# Audio-Out.net
KiCad netlist of a schematic drawn in Altium Designer
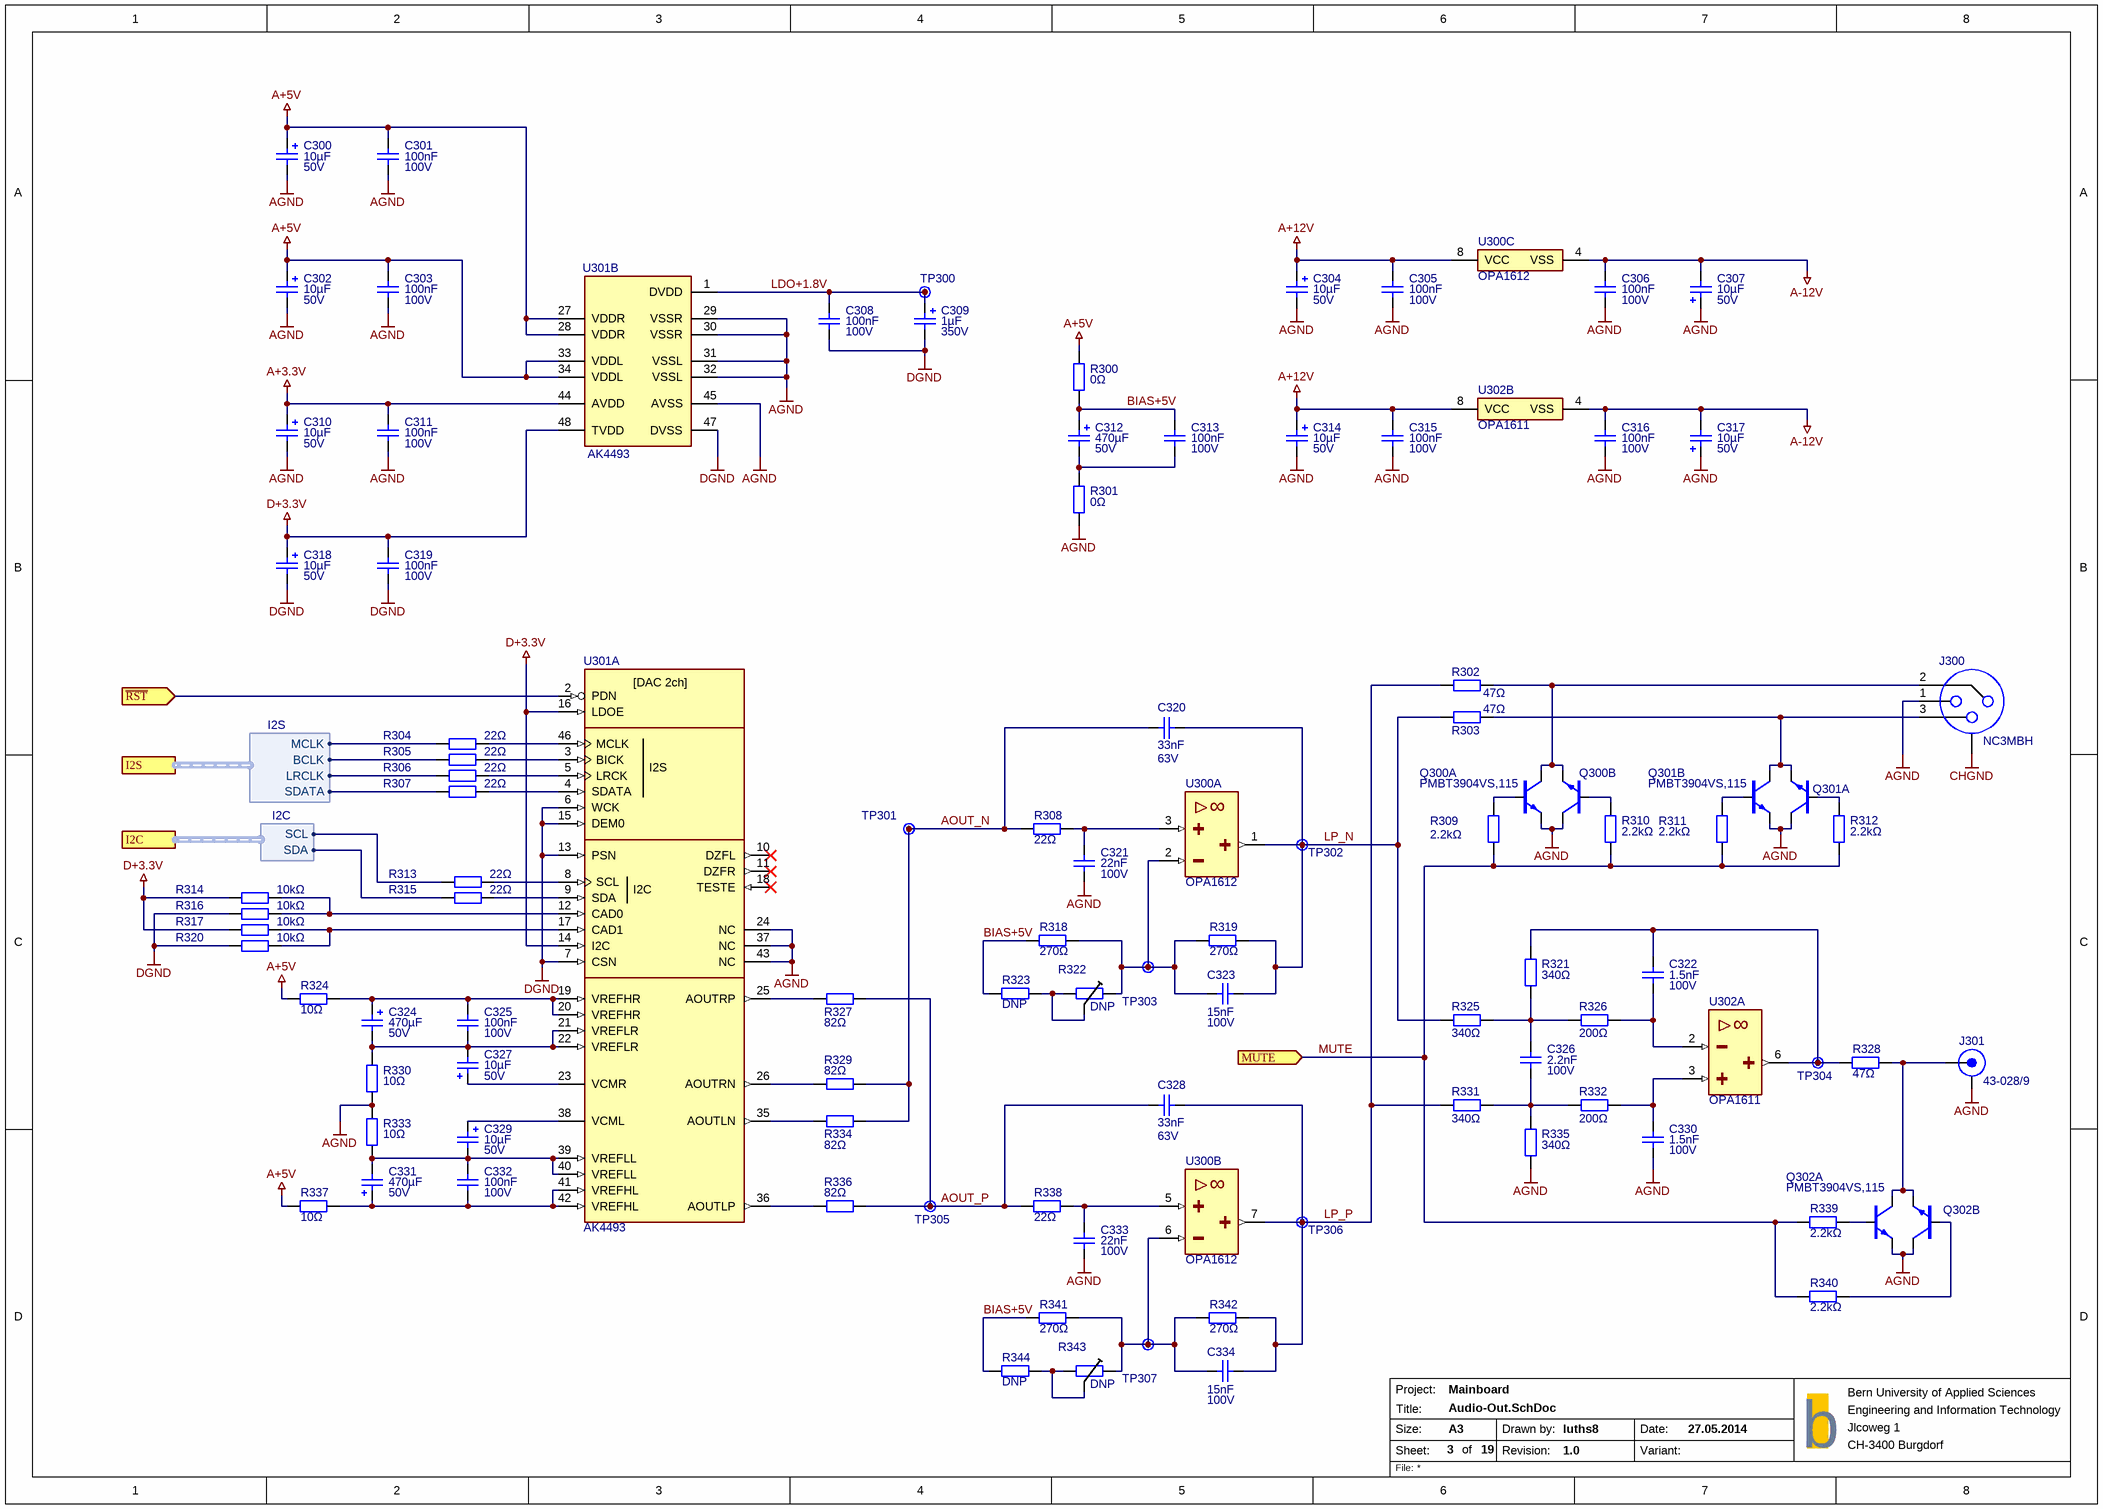
[diagram p0: Audio-Out.SchDoc]

(export (version "E")
  (design (tool "Eeschema 10.0.6"))
  (components
    (comp (ref "C300")
      (value "10µF")
      (footprint "CAP-5-11.5-2")
      (description "Elektrolytic Capacitor")
      (fields (field (name "VOLTAGE") "50V") (field (name "MANUFACTURER PART NO.") "EEU-FR1H100"))
      (libsource (lib "Audio-Streamer") (part "Capacitor Electrolytic"))
    )
    (comp (ref "C301")
      (value "100nF")
      (footprint "CAP_WIMA_MKP4F")
      (description "Ceramic Capacitor")
      (fields (field (name "VOLTAGE") "100V") (field (name "MANUFACTURER PART NO.") "MKP2D031001F00KF00"))
      (libsource (lib "Audio-Streamer") (part "Capacitor Ceramic"))
    )
    (comp (ref "C302")
      (value "10µF")
      (footprint "CAP-5-11.5-2")
      (description "Elektrolytic Capacitor")
      (fields (field (name "VOLTAGE") "50V") (field (name "MANUFACTURER PART NO.") "EEU-FR1H100"))
      (libsource (lib "Audio-Streamer") (part "Capacitor Electrolytic"))
    )
    (comp (ref "C303")
      (value "100nF")
      (footprint "CAP_WIMA_MKP4F")
      (description "Ceramic Capacitor")
      (fields (field (name "VOLTAGE") "100V") (field (name "MANUFACTURER PART NO.") "MKP2D031001F00KF00"))
      (libsource (lib "Audio-Streamer") (part "Capacitor Ceramic"))
    )
    (comp (ref "C304")
      (value "10µF")
      (footprint "CAP-5-11.5-2")
      (description "Elektrolytic Capacitor")
      (fields (field (name "VOLTAGE") "50V") (field (name "MANUFACTURER PART NO.") "EEU-FR1H100"))
      (libsource (lib "Audio-Streamer") (part "Capacitor Electrolytic"))
    )
    (comp (ref "C305")
      (value "100nF")
      (footprint "CAP_WIMA_MKP4F")
      (description "Ceramic Capacitor")
      (fields (field (name "VOLTAGE") "100V") (field (name "MANUFACTURER PART NO.") "MKP2D031001F00KF00"))
      (libsource (lib "Audio-Streamer") (part "Capacitor Ceramic"))
    )
    (comp (ref "C306")
      (value "100nF")
      (footprint "CAP_WIMA_MKP4F")
      (description "Ceramic Capacitor")
      (fields (field (name "VOLTAGE") "100V") (field (name "MANUFACTURER PART NO.") "MKP2D031001F00KF00"))
      (libsource (lib "Audio-Streamer") (part "Capacitor Ceramic"))
    )
    (comp (ref "C307")
      (value "10µF")
      (footprint "CAP-5-11.5-2")
      (description "Elektrolytic Capacitor")
      (fields (field (name "VOLTAGE") "50V") (field (name "MANUFACTURER PART NO.") "EEU-FR1H100"))
      (libsource (lib "Audio-Streamer") (part "Capacitor Electrolytic"))
    )
    (comp (ref "C308")
      (value "100nF")
      (footprint "CAP_WIMA_MKP4F")
      (description "Ceramic Capacitor")
      (fields (field (name "VOLTAGE") "100V") (field (name "MANUFACTURER PART NO.") "MKP2D031001F00KF00"))
      (libsource (lib "Audio-Streamer") (part "Capacitor Ceramic"))
    )
    (comp (ref "C309")
      (value "1µF")
      (footprint "CAP-6.3-11.2-2.5")
      (description "Elektrolytic Capacitor")
      (fields (field (name "VOLTAGE") "350V"))
      (libsource (lib "Audio-Streamer") (part "Capacitor Electrolytic"))
    )
    (comp (ref "C310")
      (value "10µF")
      (footprint "CAP-5-11.5-2")
      (description "Elektrolytic Capacitor")
      (fields (field (name "VOLTAGE") "50V") (field (name "MANUFACTURER PART NO.") "EEU-FR1H100"))
      (libsource (lib "Audio-Streamer") (part "Capacitor Electrolytic"))
    )
    (comp (ref "C311")
      (value "100nF")
      (footprint "CAP_WIMA_MKP4F")
      (description "Ceramic Capacitor")
      (fields (field (name "VOLTAGE") "100V") (field (name "MANUFACTURER PART NO.") "MKP2D031001F00KF00"))
      (libsource (lib "Audio-Streamer") (part "Capacitor Ceramic"))
    )
    (comp (ref "C312")
      (value "470µF")
      (footprint "CAP-12.5-20-5")
      (description "Elektrolytic Capacitor")
      (fields (field (name "VOLTAGE") "50V") (field (name "MANUFACTURER PART NO.") "EEU-FR1H471"))
      (libsource (lib "Audio-Streamer") (part "Capacitor Electrolytic"))
    )
    (comp (ref "C313")
      (value "100nF")
      (footprint "CAP_WIMA_MKP4F")
      (description "Ceramic Capacitor")
      (fields (field (name "VOLTAGE") "100V") (field (name "MANUFACTURER PART NO.") "MKP2D031001F00KF00"))
      (libsource (lib "Audio-Streamer") (part "Capacitor Ceramic"))
    )
    (comp (ref "C314")
      (value "10µF")
      (footprint "CAP-5-11.5-2")
      (description "Elektrolytic Capacitor")
      (fields (field (name "VOLTAGE") "50V") (field (name "MANUFACTURER PART NO.") "EEU-FR1H100"))
      (libsource (lib "Audio-Streamer") (part "Capacitor Electrolytic"))
    )
    (comp (ref "C315")
      (value "100nF")
      (footprint "CAP_WIMA_MKP4F")
      (description "Ceramic Capacitor")
      (fields (field (name "VOLTAGE") "100V") (field (name "MANUFACTURER PART NO.") "MKP2D031001F00KF00"))
      (libsource (lib "Audio-Streamer") (part "Capacitor Ceramic"))
    )
    (comp (ref "C316")
      (value "100nF")
      (footprint "CAP_WIMA_MKP4F")
      (description "Ceramic Capacitor")
      (fields (field (name "VOLTAGE") "100V") (field (name "MANUFACTURER PART NO.") "MKP2D031001F00KF00"))
      (libsource (lib "Audio-Streamer") (part "Capacitor Ceramic"))
    )
    (comp (ref "C317")
      (value "10µF")
      (footprint "CAP-5-11.5-2")
      (description "Elektrolytic Capacitor")
      (fields (field (name "VOLTAGE") "50V") (field (name "MANUFACTURER PART NO.") "EEU-FR1H100"))
      (libsource (lib "Audio-Streamer") (part "Capacitor Electrolytic"))
    )
    (comp (ref "C318")
      (value "10µF")
      (footprint "CAP-5-11.5-2")
      (description "Elektrolytic Capacitor")
      (fields (field (name "VOLTAGE") "50V") (field (name "MANUFACTURER PART NO.") "EEU-FR1H100"))
      (libsource (lib "Audio-Streamer") (part "Capacitor Electrolytic"))
    )
    (comp (ref "C319")
      (value "100nF")
      (footprint "CAP_WIMA_MKP4F")
      (description "Ceramic Capacitor")
      (fields (field (name "VOLTAGE") "100V") (field (name "MANUFACTURER PART NO.") "MKP2D031001F00KF00"))
      (libsource (lib "Audio-Streamer") (part "Capacitor Ceramic"))
    )
    (comp (ref "C320")
      (value "33nF")
      (footprint "CAP_WIMA_FKP2C")
      (description "Ceramic Capacitor")
      (fields (field (name "VOLTAGE") "63V") (field (name "MANUFACTURER PART NO.") "FKP2C023301L00HSSD"))
      (libsource (lib "Audio-Streamer") (part "Capacitor Ceramic"))
    )
    (comp (ref "C321")
      (value "22nF")
      (footprint "CAP_WIMA_FKP2C")
      (description "Ceramic Capacitor")
      (fields (field (name "VOLTAGE") "100V") (field (name "MANUFACTURER PART NO.") "FKP2D022201L00HF00"))
      (libsource (lib "Audio-Streamer") (part "Capacitor Ceramic"))
    )
    (comp (ref "C322")
      (value "1.5nF")
      (footprint "CAP_WIMA_FKP2D")
      (description "Ceramic Capacitor")
      (fields (field (name "VOLTAGE") "100V") (field (name "MANUFACTURER PART NO.") "FKP2D011501D00HSSD"))
      (libsource (lib "Audio-Streamer") (part "Capacitor Ceramic"))
    )
    (comp (ref "C323")
      (value "15nF")
      (footprint "CAP_WIMA_FKP2C")
      (description "Ceramic Capacitor")
      (fields (field (name "VOLTAGE") "100V") (field (name "MANUFACTURER PART NO.") "FKP2D021501J00HSSD"))
      (libsource (lib "Audio-Streamer") (part "Capacitor Ceramic"))
    )
    (comp (ref "C324")
      (value "470µF")
      (footprint "CAP-12.5-20-5")
      (description "Elektrolytic Capacitor")
      (fields (field (name "VOLTAGE") "50V") (field (name "MANUFACTURER PART NO.") "EEU-FR1H471"))
      (libsource (lib "Audio-Streamer") (part "Capacitor Electrolytic"))
    )
    (comp (ref "C325")
      (value "100nF")
      (footprint "CAP_WIMA_MKP4F")
      (description "Ceramic Capacitor")
      (fields (field (name "VOLTAGE") "100V") (field (name "MANUFACTURER PART NO.") "MKP2D031001F00KF00"))
      (libsource (lib "Audio-Streamer") (part "Capacitor Ceramic"))
    )
    (comp (ref "C326")
      (value "2.2nF")
      (footprint "CAP_WIMA_FKP2D")
      (description "Ceramic Capacitor")
      (fields (field (name "VOLTAGE") "100V") (field (name "MANUFACTURER PART NO.") "FKP2D012201D00HSSD"))
      (libsource (lib "Audio-Streamer") (part "Capacitor Ceramic"))
    )
    (comp (ref "C327")
      (value "10µF")
      (footprint "CAP-5-11.5-2")
      (description "Elektrolytic Capacitor")
      (fields (field (name "VOLTAGE") "50V") (field (name "MANUFACTURER PART NO.") "EEU-FR1H100"))
      (libsource (lib "Audio-Streamer") (part "Capacitor Electrolytic"))
    )
    (comp (ref "C328")
      (value "33nF")
      (footprint "CAP_WIMA_FKP2C")
      (description "Ceramic Capacitor")
      (fields (field (name "VOLTAGE") "63V") (field (name "MANUFACTURER PART NO.") "FKP2C023301L00HSSD"))
      (libsource (lib "Audio-Streamer") (part "Capacitor Ceramic"))
    )
    (comp (ref "C329")
      (value "10µF")
      (footprint "CAP-5-11.5-2")
      (description "Elektrolytic Capacitor")
      (fields (field (name "VOLTAGE") "50V") (field (name "MANUFACTURER PART NO.") "EEU-FR1H100"))
      (libsource (lib "Audio-Streamer") (part "Capacitor Electrolytic"))
    )
    (comp (ref "C330")
      (value "1.5nF")
      (footprint "CAP_WIMA_FKP2D")
      (description "Ceramic Capacitor")
      (fields (field (name "VOLTAGE") "100V") (field (name "MANUFACTURER PART NO.") "FKP2D011501D00HSSD"))
      (libsource (lib "Audio-Streamer") (part "Capacitor Ceramic"))
    )
    (comp (ref "C331")
      (value "470µF")
      (footprint "CAP-12.5-20-5")
      (description "Elektrolytic Capacitor")
      (fields (field (name "VOLTAGE") "50V") (field (name "MANUFACTURER PART NO.") "EEU-FR1H471"))
      (libsource (lib "Audio-Streamer") (part "Capacitor Electrolytic"))
    )
    (comp (ref "C332")
      (value "100nF")
      (footprint "CAP_WIMA_MKP4F")
      (description "Ceramic Capacitor")
      (fields (field (name "VOLTAGE") "100V") (field (name "MANUFACTURER PART NO.") "MKP2D031001F00KF00"))
      (libsource (lib "Audio-Streamer") (part "Capacitor Ceramic"))
    )
    (comp (ref "C333")
      (value "22nF")
      (footprint "CAP_WIMA_FKP2C")
      (description "Ceramic Capacitor")
      (fields (field (name "VOLTAGE") "100V") (field (name "MANUFACTURER PART NO.") "FKP2D022201L00HF00"))
      (libsource (lib "Audio-Streamer") (part "Capacitor Ceramic"))
    )
    (comp (ref "C334")
      (value "15nF")
      (footprint "CAP_WIMA_FKP2C")
      (description "Ceramic Capacitor")
      (fields (field (name "VOLTAGE") "100V") (field (name "MANUFACTURER PART NO.") "FKP2D021501J00HSSD"))
      (libsource (lib "Audio-Streamer") (part "Capacitor Ceramic"))
    )
    (comp (ref "J300")
      (value "NC3MBH")
      (footprint "NC3MBH")
      (description "XLR Connector Male, Panel Mount")
      (libsource (lib "Audio-Streamer") (part "Connector XLR"))
    )
    (comp (ref "J301")
      (value "43-028/9")
      (footprint "RCA-Plug")
      (description "RCA Connector")
      (libsource (lib "Audio-Streamer") (part "Connector RCA"))
    )
    (comp (ref "Q300")
      (value "PMBT3904VS,115")
      (footprint "SOT-666")
      (description "Transistor Bipolar Dual")
      (libsource (lib "") (part "Transistor Bipolar Dual_1"))
    )
    (comp (ref "Q301")
      (value "PMBT3904VS,115")
      (footprint "SOT-666")
      (description "Transistor Bipolar Dual")
      (libsource (lib "Audio-Streamer") (part "Transistor Bipolar Dual"))
    )
    (comp (ref "Q302")
      (value "PMBT3904VS,115")
      (footprint "SOT-666")
      (description "Transistor Bipolar Dual")
      (libsource (lib "") (part "Transistor Bipolar Dual_1"))
    )
    (comp (ref "R300")
      (value "0Ω")
      (footprint "SMD0603RES")
      (description "Resistor")
      (libsource (lib "") (part "Resistor_2"))
    )
    (comp (ref "R301")
      (value "0Ω")
      (footprint "SMD0603RES")
      (description "Resistor")
      (libsource (lib "") (part "Resistor_2"))
    )
    (comp (ref "R302")
      (value "47Ω")
      (footprint "SMD0603RES")
      (description "Resistor Thin Film")
      (fields (field (name "MANUFACTURER PART NO.") "TNPW060347R0BEEA"))
      (libsource (lib "") (part "Resistor_1"))
    )
    (comp (ref "R303")
      (value "47Ω")
      (footprint "SMD0603RES")
      (description "Resistor Thin Film")
      (fields (field (name "MANUFACTURER PART NO.") "TNPW060347R0BEEA"))
      (libsource (lib "") (part "Resistor_1"))
    )
    (comp (ref "R304")
      (value "22Ω")
      (footprint "SMD0603RES")
      (description "Resistor")
      (libsource (lib "") (part "Resistor_1"))
    )
    (comp (ref "R305")
      (value "22Ω")
      (footprint "SMD0603RES")
      (description "Resistor")
      (libsource (lib "") (part "Resistor_1"))
    )
    (comp (ref "R306")
      (value "22Ω")
      (footprint "SMD0603RES")
      (description "Resistor")
      (libsource (lib "") (part "Resistor_1"))
    )
    (comp (ref "R307")
      (value "22Ω")
      (footprint "SMD0603RES")
      (description "Resistor")
      (libsource (lib "") (part "Resistor_1"))
    )
    (comp (ref "R308")
      (value "22Ω")
      (footprint "SMD0603RES")
      (description "Resistor Thin Film")
      (fields (field (name "MANUFACTURER PART NO.") "TNPW060322R0BEEA"))
      (libsource (lib "") (part "Resistor_1"))
    )
    (comp (ref "R309")
      (value "2.2kΩ")
      (footprint "SMD0603RES")
      (description "Resistor")
      (libsource (lib "") (part "Resistor_3"))
    )
    (comp (ref "R310")
      (value "2.2kΩ")
      (footprint "SMD0603RES")
      (description "Resistor")
      (libsource (lib "Audio-Streamer") (part "Resistor"))
    )
    (comp (ref "R311")
      (value "2.2kΩ")
      (footprint "SMD0603RES")
      (description "Resistor")
      (libsource (lib "") (part "Resistor_3"))
    )
    (comp (ref "R312")
      (value "2.2kΩ")
      (footprint "SMD0603RES")
      (description "Resistor")
      (libsource (lib "Audio-Streamer") (part "Resistor"))
    )
    (comp (ref "R313")
      (value "22Ω")
      (footprint "SMD0603RES")
      (description "Resistor")
      (libsource (lib "") (part "Resistor_1"))
    )
    (comp (ref "R314")
      (value "10kΩ")
      (footprint "SMD0603RES")
      (description "Resistor")
      (libsource (lib "") (part "Resistor_1"))
    )
    (comp (ref "R315")
      (value "22Ω")
      (footprint "SMD0603RES")
      (description "Resistor")
      (libsource (lib "") (part "Resistor_1"))
    )
    (comp (ref "R316")
      (value "10kΩ")
      (footprint "SMD0603RES")
      (description "Resistor")
      (libsource (lib "") (part "Resistor_1"))
    )
    (comp (ref "R317")
      (value "10kΩ")
      (footprint "SMD0603RES")
      (description "Resistor")
      (libsource (lib "") (part "Resistor_1"))
    )
    (comp (ref "R318")
      (value "270Ω")
      (footprint "SMD0603RES")
      (description "Resistor Thin Film")
      (fields (field (name "MANUFACTURER PART NO.") "TNPW0603270RBEEA"))
      (libsource (lib "") (part "Resistor_1"))
    )
    (comp (ref "R319")
      (value "270Ω")
      (footprint "SMD0603RES")
      (description "Resistor Thin Film")
      (fields (field (name "MANUFACTURER PART NO.") "TNPW0603270RBEEA"))
      (libsource (lib "") (part "Resistor_1"))
    )
    (comp (ref "R320")
      (value "10kΩ")
      (footprint "SMD0603RES")
      (description "Resistor")
      (libsource (lib "") (part "Resistor_1"))
    )
    (comp (ref "R321")
      (value "340Ω")
      (footprint "SMD0603RES")
      (description "Resistor Thin Film")
      (fields (field (name "MANUFACTURER PART NO.") "TNPW0603340RBEEA"))
      (libsource (lib "") (part "Resistor_2"))
    )
    (comp (ref "R322")
      (value "DNP")
      (footprint "3266")
      (description "Trimmer (resistive)")
      (libsource (lib "Audio-Streamer") (part "Resistor Trimmer"))
    )
    (comp (ref "R323")
      (value "DNP")
      (footprint "SMD0603RES")
      (description "Resistor Thin Film")
      (libsource (lib "") (part "Resistor_1"))
    )
    (comp (ref "R324")
      (value "10Ω")
      (footprint "SMD0603RES")
      (description "Resistor")
      (libsource (lib "") (part "Resistor_1"))
    )
    (comp (ref "R325")
      (value "340Ω")
      (footprint "SMD0603RES")
      (description "Resistor Thin Film")
      (fields (field (name "MANUFACTURER PART NO.") "TNPW0603340RBEEA"))
      (libsource (lib "") (part "Resistor_1"))
    )
    (comp (ref "R326")
      (value "200Ω")
      (footprint "SMD0603RES")
      (description "Resistor Thin Film")
      (fields (field (name "MANUFACTURER PART NO.") "TNPW0603200RBEEA"))
      (libsource (lib "Audio-Streamer") (part "Resistor"))
    )
    (comp (ref "R327")
      (value "82Ω")
      (footprint "SMD0603RES")
      (description "Resistor Thin Film")
      (fields (field (name "MANUFACTURER PART NO.") "TNPW060322R0BEEA"))
      (libsource (lib "") (part "Resistor_1"))
    )
    (comp (ref "R328")
      (value "47Ω")
      (footprint "SMD0603RES")
      (description "Resistor Thin Film")
      (fields (field (name "MANUFACTURER PART NO.") "TNPW060347R0BEEA"))
      (libsource (lib "") (part "Resistor_1"))
    )
    (comp (ref "R329")
      (value "82Ω")
      (footprint "SMD0603RES")
      (description "Resistor Thin Film")
      (fields (field (name "MANUFACTURER PART NO.") "TNPW060322R0BEEA"))
      (libsource (lib "") (part "Resistor_1"))
    )
    (comp (ref "R330")
      (value "10Ω")
      (footprint "SMD0603RES")
      (description "Resistor")
      (libsource (lib "") (part "Resistor_2"))
    )
    (comp (ref "R331")
      (value "340Ω")
      (footprint "SMD0603RES")
      (description "Resistor Thin Film")
      (fields (field (name "MANUFACTURER PART NO.") "TNPW0603340RBEEA"))
      (libsource (lib "") (part "Resistor_1"))
    )
    (comp (ref "R332")
      (value "200Ω")
      (footprint "SMD0603RES")
      (description "Resistor Thin Film")
      (fields (field (name "MANUFACTURER PART NO.") "TNPW0603200RBEEA"))
      (libsource (lib "Audio-Streamer") (part "Resistor"))
    )
    (comp (ref "R333")
      (value "10Ω")
      (footprint "SMD0603RES")
      (description "Resistor")
      (libsource (lib "") (part "Resistor_2"))
    )
    (comp (ref "R334")
      (value "82Ω")
      (footprint "SMD0603RES")
      (description "Resistor Thin Film")
      (fields (field (name "MANUFACTURER PART NO.") "TNPW060322R0BEEA"))
      (libsource (lib "") (part "Resistor_1"))
    )
    (comp (ref "R335")
      (value "340Ω")
      (footprint "SMD0603RES")
      (description "Resistor Thin Film")
      (fields (field (name "MANUFACTURER PART NO.") "TNPW0603340RBEEA"))
      (libsource (lib "") (part "Resistor_3"))
    )
    (comp (ref "R336")
      (value "82Ω")
      (footprint "SMD0603RES")
      (description "Resistor Thin Film")
      (fields (field (name "MANUFACTURER PART NO.") "TNPW060322R0BEEA"))
      (libsource (lib "") (part "Resistor_1"))
    )
    (comp (ref "R337")
      (value "10Ω")
      (footprint "SMD0603RES")
      (description "Resistor")
      (libsource (lib "Audio-Streamer") (part "Resistor"))
    )
    (comp (ref "R338")
      (value "22Ω")
      (footprint "SMD0603RES")
      (description "Resistor Thin Film")
      (fields (field (name "MANUFACTURER PART NO.") "TNPW060322R0BEEA"))
      (libsource (lib "") (part "Resistor_1"))
    )
    (comp (ref "R339")
      (value "2.2kΩ")
      (footprint "SMD0603RES")
      (description "Resistor")
      (libsource (lib "") (part "Resistor_1"))
    )
    (comp (ref "R340")
      (value "2.2kΩ")
      (footprint "SMD0603RES")
      (description "Resistor")
      (libsource (lib "") (part "Resistor_1"))
    )
    (comp (ref "R341")
      (value "270Ω")
      (footprint "SMD0603RES")
      (description "Resistor Thin Film")
      (fields (field (name "MANUFACTURER PART NO.") "TNPW0603270RBEEA"))
      (libsource (lib "") (part "Resistor_1"))
    )
    (comp (ref "R342")
      (value "270Ω")
      (footprint "SMD0603RES")
      (description "Resistor Thin Film")
      (fields (field (name "MANUFACTURER PART NO.") "TNPW0603270RBEEA"))
      (libsource (lib "") (part "Resistor_1"))
    )
    (comp (ref "R343")
      (value "DNP")
      (footprint "3266")
      (description "Trimmer (resistive)")
      (libsource (lib "Audio-Streamer") (part "Resistor Trimmer"))
    )
    (comp (ref "R344")
      (value "DNP")
      (footprint "SMD0603RES")
      (description "Resistor Thin Film")
      (libsource (lib "") (part "Resistor_1"))
    )
    (comp (ref "TP300")
      (value "Testpoint")
      (footprint "TP")
      (libsource (lib "Audio-Streamer") (part "Testpoint"))
    )
    (comp (ref "TP301")
      (value "Testpoint")
      (footprint "TP")
      (libsource (lib "Audio-Streamer") (part "Testpoint"))
    )
    (comp (ref "TP302")
      (value "Testpoint")
      (footprint "TP")
      (libsource (lib "Audio-Streamer") (part "Testpoint"))
    )
    (comp (ref "TP303")
      (value "Testpoint")
      (footprint "TP")
      (libsource (lib "Audio-Streamer") (part "Testpoint"))
    )
    (comp (ref "TP304")
      (value "Testpoint")
      (footprint "TP")
      (libsource (lib "Audio-Streamer") (part "Testpoint"))
    )
    (comp (ref "TP305")
      (value "Testpoint")
      (footprint "TP")
      (libsource (lib "Audio-Streamer") (part "Testpoint"))
    )
    (comp (ref "TP306")
      (value "Testpoint")
      (footprint "TP")
      (libsource (lib "Audio-Streamer") (part "Testpoint"))
    )
    (comp (ref "TP307")
      (value "Testpoint")
      (footprint "TP")
      (libsource (lib "Audio-Streamer") (part "Testpoint"))
    )
    (comp (ref "U300")
      (value "OPA1612")
      (footprint "SOIC8")
      (description "SoundPlus Operational Amplifier")
      (fields (field (name "MANUFACTURER PART NO.") "OPA1612AIDR"))
      (libsource (lib "Audio-Streamer") (part "OPA1612"))
    )
    (comp (ref "U301")
      (value "AK4493")
      (footprint "LQFP48")
      (description "32-Bit 2ch Audio DAC")
      (fields (field (name "MANUFACTURER PART NO.") "AK4493EQ"))
      (libsource (lib "Audio-Streamer") (part "AK4493"))
    )
    (comp (ref "U302")
      (value "OPA1611")
      (footprint "SOIC8")
      (description "SoundPlus Operational Amplifier")
      (fields (field (name "MANUFACTURER PART NO.") "OPA1611AIDR"))
      (libsource (lib "Audio-Streamer") (part "OPA1611"))
    )
  )
  (nets
    (net (code "3") (name "/AOUT_N") (class "Default")
      (node (ref "C320") (pin "1") (pinfunction "1_1") (pintype "passive"))
      (node (ref "R308") (pin "2") (pinfunction "2_2") (pintype "passive"))
      (node (ref "R329") (pin "1") (pinfunction "1_1") (pintype "passive"))
      (node (ref "R334") (pin "1") (pinfunction "1_1") (pintype "passive"))
      (node (ref "TP301") (pin "1") (pinfunction "1_1") (pintype "passive"))
    )
    (net (code "4") (name "/AOUT_P") (class "Default")
      (node (ref "C328") (pin "1") (pinfunction "1_1") (pintype "passive"))
      (node (ref "R327") (pin "1") (pinfunction "1_1") (pintype "passive"))
      (node (ref "R336") (pin "1") (pinfunction "1_1") (pintype "passive"))
      (node (ref "R338") (pin "2") (pinfunction "2_2") (pintype "passive"))
      (node (ref "TP305") (pin "1") (pinfunction "1_1") (pintype "passive"))
    )
    (net (code "5") (name "/BCLK") (class "Default")
      (node (ref "R305") (pin "2") (pinfunction "2_2") (pintype "passive"))
    )
    (net (code "6") (name "/BIAS+5V") (class "Default")
      (node (ref "C312") (pin "P") (pinfunction "P_P") (pintype "passive"))
      (node (ref "C313") (pin "2") (pinfunction "q_2") (pintype "passive"))
      (node (ref "R300") (pin "2") (pinfunction "2_2") (pintype "passive"))
      (node (ref "R318") (pin "2") (pinfunction "2_2") (pintype "passive"))
      (node (ref "R323") (pin "2") (pinfunction "2_2") (pintype "passive"))
      (node (ref "R341") (pin "2") (pinfunction "2_2") (pintype "passive"))
      (node (ref "R344") (pin "2") (pinfunction "2_2") (pintype "passive"))
    )
    (net (code "7") (name "/LDO+1.8V") (class "Default")
      (node (ref "C308") (pin "2") (pinfunction "q_2") (pintype "passive"))
      (node (ref "C309") (pin "P") (pinfunction "P_P") (pintype "passive"))
      (node (ref "TP300") (pin "1") (pinfunction "1_1") (pintype "passive"))
      (node (ref "U301") (pin "1") (pinfunction "DVDD_1") (pintype "power_in"))
    )
    (net (code "8") (name "/LP_N") (class "Default")
      (node (ref "C320") (pin "2") (pinfunction "q_2") (pintype "passive"))
      (node (ref "C323") (pin "1") (pinfunction "1_1") (pintype "passive"))
      (node (ref "R303") (pin "2") (pinfunction "2_2") (pintype "passive"))
      (node (ref "R319") (pin "1") (pinfunction "1_1") (pintype "passive"))
      (node (ref "R325") (pin "2") (pinfunction "2_2") (pintype "passive"))
      (node (ref "TP302") (pin "1") (pinfunction "1_1") (pintype "passive"))
      (node (ref "U300") (pin "1") (pinfunction "OUTA_1") (pintype "output"))
    )
    (net (code "9") (name "/LP_P") (class "Default")
      (node (ref "C328") (pin "2") (pinfunction "q_2") (pintype "passive"))
      (node (ref "C334") (pin "1") (pinfunction "1_1") (pintype "passive"))
      (node (ref "R302") (pin "2") (pinfunction "2_2") (pintype "passive"))
      (node (ref "R331") (pin "2") (pinfunction "2_2") (pintype "passive"))
      (node (ref "R342") (pin "1") (pinfunction "1_1") (pintype "passive"))
      (node (ref "TP306") (pin "1") (pinfunction "1_1") (pintype "passive"))
      (node (ref "U300") (pin "7") (pinfunction "OUTB_7") (pintype "output"))
    )
    (net (code "10") (name "/LRCLK") (class "Default")
      (node (ref "R306") (pin "2") (pinfunction "2_2") (pintype "passive"))
    )
    (net (code "11") (name "/MCLK") (class "Default")
      (node (ref "R304") (pin "2") (pinfunction "2_2") (pintype "passive"))
    )
    (net (code "12") (name "/MUTE") (class "Default")
      (node (ref "R309") (pin "1") (pinfunction "1_1") (pintype "passive"))
      (node (ref "R310") (pin "1") (pinfunction "1_1") (pintype "passive"))
      (node (ref "R311") (pin "1") (pinfunction "1_1") (pintype "passive"))
      (node (ref "R312") (pin "1") (pinfunction "1_1") (pintype "passive"))
      (node (ref "R339") (pin "2") (pinfunction "2_2") (pintype "passive"))
      (node (ref "R340") (pin "2") (pinfunction "2_2") (pintype "passive"))
    )
    (net (code "13") (name "/SCL") (class "Default")
      (node (ref "R313") (pin "2") (pinfunction "2_2") (pintype "passive"))
    )
    (net (code "14") (name "/SDA") (class "Default")
      (node (ref "R315") (pin "2") (pinfunction "2_2") (pintype "passive"))
    )
    (net (code "15") (name "/SDATA") (class "Default")
      (node (ref "R307") (pin "2") (pinfunction "2_2") (pintype "passive"))
    )
    (net (code "18") (name "/~{RST}") (class "Default")
      (node (ref "U301") (pin "2") (pinfunction "PDN_2") (pintype "input"))
    )
    (net (code "19") (name "A+3.3V") (class "Default")
      (node (ref "C310") (pin "P") (pinfunction "P_P") (pintype "passive"))
      (node (ref "C311") (pin "2") (pinfunction "q_2") (pintype "passive"))
      (node (ref "U301") (pin "44") (pinfunction "AVDD_44") (pintype "power_in"))
    )
    (net (code "20") (name "A+5V") (class "Default")
      (node (ref "C300") (pin "P") (pinfunction "P_P") (pintype "passive"))
      (node (ref "C301") (pin "2") (pinfunction "q_2") (pintype "passive"))
      (node (ref "C302") (pin "P") (pinfunction "P_P") (pintype "passive"))
      (node (ref "C303") (pin "2") (pinfunction "q_2") (pintype "passive"))
      (node (ref "R300") (pin "1") (pinfunction "1_1") (pintype "passive"))
      (node (ref "R324") (pin "2") (pinfunction "2_2") (pintype "passive"))
      (node (ref "R337") (pin "1") (pinfunction "1_1") (pintype "passive"))
      (node (ref "U301") (pin "27") (pinfunction "VDDR_27") (pintype "power_in"))
      (node (ref "U301") (pin "28") (pinfunction "VDDR_28") (pintype "power_in"))
      (node (ref "U301") (pin "33") (pinfunction "VDDL_33") (pintype "passive"))
      (node (ref "U301") (pin "34") (pinfunction "VDDL_34") (pintype "passive"))
    )
    (net (code "21") (name "A+12V") (class "Default")
      (node (ref "C304") (pin "P") (pinfunction "P_P") (pintype "passive"))
      (node (ref "C305") (pin "2") (pinfunction "q_2") (pintype "passive"))
      (node (ref "C314") (pin "P") (pinfunction "P_P") (pintype "passive"))
      (node (ref "C315") (pin "2") (pinfunction "q_2") (pintype "passive"))
      (node (ref "U300") (pin "8") (pinfunction "VCC_8") (pintype "power_in"))
      (node (ref "U302") (pin "8") (pinfunction "VCC_8") (pintype "power_in"))
    )
    (net (code "22") (name "A-12V") (class "Default")
      (node (ref "C306") (pin "1") (pinfunction "1_1") (pintype "passive"))
      (node (ref "C307") (pin "M") (pinfunction "q_M") (pintype "passive"))
      (node (ref "C316") (pin "1") (pinfunction "1_1") (pintype "passive"))
      (node (ref "C317") (pin "M") (pinfunction "q_M") (pintype "passive"))
      (node (ref "U300") (pin "4") (pinfunction "VSS_4") (pintype "power_in"))
      (node (ref "U302") (pin "4") (pinfunction "VSS_4") (pintype "power_in"))
    )
    (net (code "23") (name "AGND") (class "Default")
      (node (ref "C300") (pin "M") (pinfunction "q_M") (pintype "passive"))
      (node (ref "C301") (pin "1") (pinfunction "1_1") (pintype "passive"))
      (node (ref "C302") (pin "M") (pinfunction "q_M") (pintype "passive"))
      (node (ref "C303") (pin "1") (pinfunction "1_1") (pintype "passive"))
      (node (ref "C304") (pin "M") (pinfunction "q_M") (pintype "passive"))
      (node (ref "C305") (pin "1") (pinfunction "1_1") (pintype "passive"))
      (node (ref "C306") (pin "2") (pinfunction "q_2") (pintype "passive"))
      (node (ref "C307") (pin "P") (pinfunction "P_P") (pintype "passive"))
      (node (ref "C310") (pin "M") (pinfunction "q_M") (pintype "passive"))
      (node (ref "C311") (pin "1") (pinfunction "1_1") (pintype "passive"))
      (node (ref "C314") (pin "M") (pinfunction "q_M") (pintype "passive"))
      (node (ref "C315") (pin "1") (pinfunction "1_1") (pintype "passive"))
      (node (ref "C316") (pin "2") (pinfunction "q_2") (pintype "passive"))
      (node (ref "C317") (pin "P") (pinfunction "P_P") (pintype "passive"))
      (node (ref "C321") (pin "1") (pinfunction "1_1") (pintype "passive"))
      (node (ref "C330") (pin "1") (pinfunction "1_1") (pintype "passive"))
      (node (ref "C333") (pin "1") (pinfunction "1_1") (pintype "passive"))
      (node (ref "J300") (pin "1") (pinfunction "1_1") (pintype "passive"))
      (node (ref "J301") (pin "2") (pinfunction "2_2") (pintype "passive"))
      (node (ref "Q300") (pin "1") (pinfunction "1_1") (pintype "passive"))
      (node (ref "Q300") (pin "3") (pinfunction "3_3") (pintype "passive"))
      (node (ref "Q301") (pin "4") (pinfunction "4_4") (pintype "passive"))
      (node (ref "Q301") (pin "6") (pinfunction "6_6") (pintype "passive"))
      (node (ref "Q302") (pin "1") (pinfunction "1_1") (pintype "passive"))
      (node (ref "Q302") (pin "3") (pinfunction "3_3") (pintype "passive"))
      (node (ref "R301") (pin "2") (pinfunction "2_2") (pintype "passive"))
      (node (ref "R330") (pin "2") (pinfunction "2_2") (pintype "passive"))
      (node (ref "R333") (pin "1") (pinfunction "1_1") (pintype "passive"))
      (node (ref "R335") (pin "1") (pinfunction "1_1") (pintype "passive"))
      (node (ref "U301") (pin "24") (pinfunction "NC_24") (pintype "passive"))
      (node (ref "U301") (pin "29") (pinfunction "VSSR_29") (pintype "power_in"))
      (node (ref "U301") (pin "30") (pinfunction "VSSR_30") (pintype "power_in"))
      (node (ref "U301") (pin "31") (pinfunction "VSSL_31") (pintype "power_in"))
      (node (ref "U301") (pin "32") (pinfunction "VSSL_32") (pintype "power_in"))
      (node (ref "U301") (pin "37") (pinfunction "NC_37") (pintype "passive"))
      (node (ref "U301") (pin "43") (pinfunction "NC_43") (pintype "passive"))
      (node (ref "U301") (pin "45") (pinfunction "AVSS_45") (pintype "power_in"))
    )
    (net (code "24") (name "CHGND") (class "Default")
      (node (ref "J300") (pin "0") (pinfunction "0_0") (pintype "passive"))
    )
    (net (code "25") (name "D+3.3V") (class "Default")
      (node (ref "C318") (pin "P") (pinfunction "P_P") (pintype "passive"))
      (node (ref "C319") (pin "2") (pinfunction "q_2") (pintype "passive"))
      (node (ref "R314") (pin "2") (pinfunction "2_2") (pintype "passive"))
      (node (ref "R317") (pin "2") (pinfunction "2_2") (pintype "passive"))
      (node (ref "U301") (pin "14") (pinfunction "I2C_14") (pintype "input"))
      (node (ref "U301") (pin "16") (pinfunction "LDOE_16") (pintype "input"))
      (node (ref "U301") (pin "48") (pinfunction "TVDD_48") (pintype "power_in"))
    )
    (net (code "26") (name "DGND") (class "Default")
      (node (ref "C308") (pin "1") (pinfunction "1_1") (pintype "passive"))
      (node (ref "C309") (pin "M") (pinfunction "q_M") (pintype "passive"))
      (node (ref "C318") (pin "M") (pinfunction "q_M") (pintype "passive"))
      (node (ref "C319") (pin "1") (pinfunction "1_1") (pintype "passive"))
      (node (ref "R316") (pin "2") (pinfunction "2_2") (pintype "passive"))
      (node (ref "R320") (pin "2") (pinfunction "2_2") (pintype "passive"))
      (node (ref "U301") (pin "13") (pinfunction "PSN_13") (pintype "input"))
      (node (ref "U301") (pin "15") (pinfunction "DEM0_15") (pintype "input"))
      (node (ref "U301") (pin "47") (pinfunction "DVSS_47") (pintype "power_in"))
      (node (ref "U301") (pin "6") (pinfunction "WCK_6") (pintype "input"))
      (node (ref "U301") (pin "7") (pinfunction "CSN_7") (pintype "input"))
    )
    (net (code "27") (name "Net-(C312-q)") (class "Default")
      (node (ref "C312") (pin "M") (pinfunction "q_M") (pintype "passive"))
      (node (ref "C313") (pin "1") (pinfunction "1_1") (pintype "passive"))
      (node (ref "R301") (pin "1") (pinfunction "1_1") (pintype "passive"))
    )
    (net (code "28") (name "Net-(C321-q)") (class "Default")
      (node (ref "C321") (pin "2") (pinfunction "q_2") (pintype "passive"))
      (node (ref "R308") (pin "1") (pinfunction "1_1") (pintype "passive"))
      (node (ref "U300") (pin "3") (pinfunction "PINA_3") (pintype "input"))
    )
    (net (code "29") (name "Net-(C322-q)") (class "Default")
      (node (ref "C322") (pin "2") (pinfunction "q_2") (pintype "passive"))
      (node (ref "R326") (pin "2") (pinfunction "2_2") (pintype "passive"))
      (node (ref "U302") (pin "2") (pinfunction "NIN_2") (pintype "input"))
    )
    (net (code "30") (name "Net-(C323-q)") (class "Default")
      (node (ref "C323") (pin "2") (pinfunction "q_2") (pintype "passive"))
      (node (ref "R318") (pin "1") (pinfunction "1_1") (pintype "passive"))
      (node (ref "R319") (pin "2") (pinfunction "2_2") (pintype "passive"))
      (node (ref "R322") (pin "1") (pinfunction "1_1") (pintype "passive"))
      (node (ref "TP303") (pin "1") (pinfunction "1_1") (pintype "passive"))
      (node (ref "U300") (pin "2") (pinfunction "NINA_2") (pintype "input"))
    )
    (net (code "31") (name "Net-(C324-q)") (class "Default")
      (node (ref "C324") (pin "M") (pinfunction "q_M") (pintype "passive"))
      (node (ref "C325") (pin "1") (pinfunction "1_1") (pintype "passive"))
      (node (ref "C327") (pin "M") (pinfunction "q_M") (pintype "passive"))
      (node (ref "R330") (pin "1") (pinfunction "1_1") (pintype "passive"))
      (node (ref "U301") (pin "21") (pinfunction "VREFLR_21") (pintype "input"))
      (node (ref "U301") (pin "22") (pinfunction "VREFLR_22") (pintype "input"))
    )
    (net (code "32") (name "Net-(C325-q)") (class "Default")
      (node (ref "C324") (pin "P") (pinfunction "P_P") (pintype "passive"))
      (node (ref "C325") (pin "2") (pinfunction "q_2") (pintype "passive"))
      (node (ref "R324") (pin "1") (pinfunction "1_1") (pintype "passive"))
      (node (ref "U301") (pin "19") (pinfunction "VREFHR_19") (pintype "input"))
      (node (ref "U301") (pin "20") (pinfunction "VREFHR_20") (pintype "input"))
    )
    (net (code "33") (name "Net-(C326-Pad1)") (class "Default")
      (node (ref "C326") (pin "1") (pinfunction "1_1") (pintype "passive"))
      (node (ref "R321") (pin "2") (pinfunction "2_2") (pintype "passive"))
      (node (ref "R325") (pin "1") (pinfunction "1_1") (pintype "passive"))
      (node (ref "R326") (pin "1") (pinfunction "1_1") (pintype "passive"))
    )
    (net (code "34") (name "Net-(C326-q)") (class "Default")
      (node (ref "C326") (pin "2") (pinfunction "q_2") (pintype "passive"))
      (node (ref "R331") (pin "1") (pinfunction "1_1") (pintype "passive"))
      (node (ref "R332") (pin "1") (pinfunction "1_1") (pintype "passive"))
      (node (ref "R335") (pin "2") (pinfunction "2_2") (pintype "passive"))
    )
    (net (code "35") (name "Net-(C329-q)") (class "Default")
      (node (ref "C329") (pin "M") (pinfunction "q_M") (pintype "passive"))
      (node (ref "C331") (pin "M") (pinfunction "q_M") (pintype "passive"))
      (node (ref "C332") (pin "2") (pinfunction "q_2") (pintype "passive"))
      (node (ref "R333") (pin "2") (pinfunction "2_2") (pintype "passive"))
      (node (ref "U301") (pin "39") (pinfunction "VREFLL_39") (pintype "input"))
      (node (ref "U301") (pin "40") (pinfunction "VREFLL_40") (pintype "input"))
    )
    (net (code "36") (name "Net-(C330-q)") (class "Default")
      (node (ref "C330") (pin "2") (pinfunction "q_2") (pintype "passive"))
      (node (ref "R332") (pin "2") (pinfunction "2_2") (pintype "passive"))
      (node (ref "U302") (pin "3") (pinfunction "PIN_3") (pintype "input"))
    )
    (net (code "37") (name "Net-(C331-PadP)") (class "Default")
      (node (ref "C331") (pin "P") (pinfunction "P_P") (pintype "passive"))
      (node (ref "C332") (pin "1") (pinfunction "1_1") (pintype "passive"))
      (node (ref "R337") (pin "2") (pinfunction "2_2") (pintype "passive"))
      (node (ref "U301") (pin "41") (pinfunction "VREFHL_41") (pintype "input"))
      (node (ref "U301") (pin "42") (pinfunction "VREFHL_42") (pintype "input"))
    )
    (net (code "38") (name "Net-(C333-q)") (class "Default")
      (node (ref "C333") (pin "2") (pinfunction "q_2") (pintype "passive"))
      (node (ref "R338") (pin "1") (pinfunction "1_1") (pintype "passive"))
      (node (ref "U300") (pin "5") (pinfunction "PINB_5") (pintype "input"))
    )
    (net (code "39") (name "Net-(C334-q)") (class "Default")
      (node (ref "C334") (pin "2") (pinfunction "q_2") (pintype "passive"))
      (node (ref "R341") (pin "1") (pinfunction "1_1") (pintype "passive"))
      (node (ref "R342") (pin "2") (pinfunction "2_2") (pintype "passive"))
      (node (ref "R343") (pin "1") (pinfunction "1_1") (pintype "passive"))
      (node (ref "TP307") (pin "1") (pinfunction "1_1") (pintype "passive"))
      (node (ref "U300") (pin "6") (pinfunction "NINB_6") (pintype "input"))
    )
    (net (code "40") (name "Net-(J300-Pad2)") (class "Default")
      (node (ref "J300") (pin "2") (pinfunction "2_2") (pintype "passive"))
      (node (ref "Q300") (pin "4") (pinfunction "4_4") (pintype "passive"))
      (node (ref "Q300") (pin "6") (pinfunction "6_6") (pintype "passive"))
      (node (ref "R302") (pin "1") (pinfunction "1_1") (pintype "passive"))
    )
    (net (code "41") (name "Net-(J300-Pad3)") (class "Default")
      (node (ref "J300") (pin "3") (pinfunction "3_3") (pintype "passive"))
      (node (ref "Q301") (pin "1") (pinfunction "1_1") (pintype "passive"))
      (node (ref "Q301") (pin "3") (pinfunction "3_3") (pintype "passive"))
      (node (ref "R303") (pin "1") (pinfunction "1_1") (pintype "passive"))
    )
    (net (code "42") (name "Net-(J301-Pad1)") (class "Default")
      (node (ref "J301") (pin "1") (pinfunction "1_1") (pintype "passive"))
      (node (ref "Q302") (pin "4") (pinfunction "4_4") (pintype "passive"))
      (node (ref "Q302") (pin "6") (pinfunction "6_6") (pintype "passive"))
      (node (ref "R328") (pin "1") (pinfunction "1_1") (pintype "passive"))
    )
    (net (code "43") (name "Net-(Q300-Pad2)") (class "Default")
      (node (ref "Q300") (pin "2") (pinfunction "2_2") (pintype "passive"))
      (node (ref "R309") (pin "2") (pinfunction "2_2") (pintype "passive"))
    )
    (net (code "44") (name "Net-(Q300-Pad5)") (class "Default")
      (node (ref "Q300") (pin "5") (pinfunction "5_5") (pintype "passive"))
      (node (ref "R310") (pin "2") (pinfunction "2_2") (pintype "passive"))
    )
    (net (code "45") (name "Net-(Q301-Pad2)") (class "Default")
      (node (ref "Q301") (pin "2") (pinfunction "2_2") (pintype "passive"))
      (node (ref "R312") (pin "2") (pinfunction "2_2") (pintype "passive"))
    )
    (net (code "46") (name "Net-(Q301-Pad5)") (class "Default")
      (node (ref "Q301") (pin "5") (pinfunction "5_5") (pintype "passive"))
      (node (ref "R311") (pin "2") (pinfunction "2_2") (pintype "passive"))
    )
    (net (code "47") (name "Net-(Q302-Pad2)") (class "Default")
      (node (ref "Q302") (pin "2") (pinfunction "2_2") (pintype "passive"))
      (node (ref "R339") (pin "1") (pinfunction "1_1") (pintype "passive"))
    )
    (net (code "48") (name "Net-(Q302-Pad5)") (class "Default")
      (node (ref "Q302") (pin "5") (pinfunction "5_5") (pintype "passive"))
      (node (ref "R340") (pin "1") (pinfunction "1_1") (pintype "passive"))
    )
    (net (code "49") (name "Net-(R322-Pad2)") (class "Default")
      (node (ref "R322") (pin "2") (pinfunction "2_2") (pintype "passive"))
      (node (ref "R322") (pin "3") (pinfunction "3_3") (pintype "passive"))
      (node (ref "R323") (pin "1") (pinfunction "1_1") (pintype "passive"))
    )
    (net (code "50") (name "Net-(R343-Pad2)") (class "Default")
      (node (ref "R343") (pin "2") (pinfunction "2_2") (pintype "passive"))
      (node (ref "R343") (pin "3") (pinfunction "3_3") (pintype "passive"))
      (node (ref "R344") (pin "1") (pinfunction "1_1") (pintype "passive"))
    )
    (net (code "51") (name "Net-(U301A-AOUTLN)") (class "Default")
      (node (ref "R334") (pin "2") (pinfunction "2_2") (pintype "passive"))
      (node (ref "U301") (pin "35") (pinfunction "AOUTLN_35") (pintype "output"))
    )
    (net (code "52") (name "Net-(U301A-AOUTLP)") (class "Default")
      (node (ref "R336") (pin "2") (pinfunction "2_2") (pintype "passive"))
      (node (ref "U301") (pin "36") (pinfunction "AOUTLP_36") (pintype "output"))
    )
    (net (code "53") (name "Net-(U301A-AOUTRN)") (class "Default")
      (node (ref "R329") (pin "2") (pinfunction "2_2") (pintype "passive"))
      (node (ref "U301") (pin "26") (pinfunction "AOUTRN_26") (pintype "output"))
    )
    (net (code "54") (name "Net-(U301A-AOUTRP)") (class "Default")
      (node (ref "R327") (pin "2") (pinfunction "2_2") (pintype "passive"))
      (node (ref "U301") (pin "25") (pinfunction "AOUTRP_25") (pintype "output"))
    )
    (net (code "55") (name "Net-(U301A-BICK)") (class "Default")
      (node (ref "R305") (pin "1") (pinfunction "1_1") (pintype "passive"))
      (node (ref "U301") (pin "3") (pinfunction "BICK_3") (pintype "input"))
    )
    (net (code "56") (name "Net-(U301A-CAD0)") (class "Default")
      (node (ref "R314") (pin "1") (pinfunction "1_1") (pintype "passive"))
      (node (ref "R316") (pin "1") (pinfunction "1_1") (pintype "passive"))
      (node (ref "U301") (pin "12") (pinfunction "CAD0_12") (pintype "input"))
    )
    (net (code "57") (name "Net-(U301A-CAD1)") (class "Default")
      (node (ref "R317") (pin "1") (pinfunction "1_1") (pintype "passive"))
      (node (ref "R320") (pin "1") (pinfunction "1_1") (pintype "passive"))
      (node (ref "U301") (pin "17") (pinfunction "CAD1_17") (pintype "input"))
    )
    (net (code "58") (name "Net-(U301A-LRCK)") (class "Default")
      (node (ref "R306") (pin "1") (pinfunction "1_1") (pintype "passive"))
      (node (ref "U301") (pin "5") (pinfunction "LRCK_5") (pintype "input"))
    )
    (net (code "59") (name "Net-(U301A-MCLK)") (class "Default")
      (node (ref "R304") (pin "1") (pinfunction "1_1") (pintype "passive"))
      (node (ref "U301") (pin "46") (pinfunction "MCLK_46") (pintype "input"))
    )
    (net (code "60") (name "Net-(U301A-SCL)") (class "Default")
      (node (ref "R313") (pin "1") (pinfunction "1_1") (pintype "passive"))
      (node (ref "U301") (pin "8") (pinfunction "SCL_8") (pintype "input"))
    )
    (net (code "61") (name "Net-(U301A-SDA)") (class "Default")
      (node (ref "R315") (pin "1") (pinfunction "1_1") (pintype "passive"))
      (node (ref "U301") (pin "9") (pinfunction "SDA_9") (pintype "input"))
    )
    (net (code "62") (name "Net-(U301A-SDATA)") (class "Default")
      (node (ref "R307") (pin "1") (pinfunction "1_1") (pintype "passive"))
      (node (ref "U301") (pin "4") (pinfunction "SDATA_4") (pintype "input"))
    )
    (net (code "63") (name "Net-(U301A-VCML)") (class "Default")
      (node (ref "C329") (pin "P") (pinfunction "P_P") (pintype "passive"))
      (node (ref "U301") (pin "38") (pinfunction "VCML_38") (pintype "power_in"))
    )
    (net (code "64") (name "Net-(U301A-VCMR)") (class "Default")
      (node (ref "C327") (pin "P") (pinfunction "P_P") (pintype "passive"))
      (node (ref "U301") (pin "23") (pinfunction "VCMR_23") (pintype "power_in"))
    )
    (net (code "65") (name "Net-(U302A-OUT)") (class "Default")
      (node (ref "C322") (pin "1") (pinfunction "1_1") (pintype "passive"))
      (node (ref "R321") (pin "1") (pinfunction "1_1") (pintype "passive"))
      (node (ref "R328") (pin "2") (pinfunction "2_2") (pintype "passive"))
      (node (ref "TP304") (pin "1") (pinfunction "1_1") (pintype "passive"))
      (node (ref "U302") (pin "6") (pinfunction "OUT_6") (pintype "output"))
    )
    (net (code "66") (name "unconnected-(U301A-DZFL-Pad10)") (class "Default")
      (node (ref "U301") (pin "10") (pinfunction "DZFL_10") (pintype "output+no_connect"))
    )
    (net (code "67") (name "unconnected-(U301A-DZFR-Pad11)") (class "Default")
      (node (ref "U301") (pin "11") (pinfunction "DZFR_11") (pintype "output+no_connect"))
    )
    (net (code "68") (name "unconnected-(U301A-TESTE-Pad18)") (class "Default")
      (node (ref "U301") (pin "18") (pinfunction "TESTE_18") (pintype "input+no_connect"))
    )
  )
)
